# Sheet1.net
KiCad netlist of a schematic drawn in Altium Designer
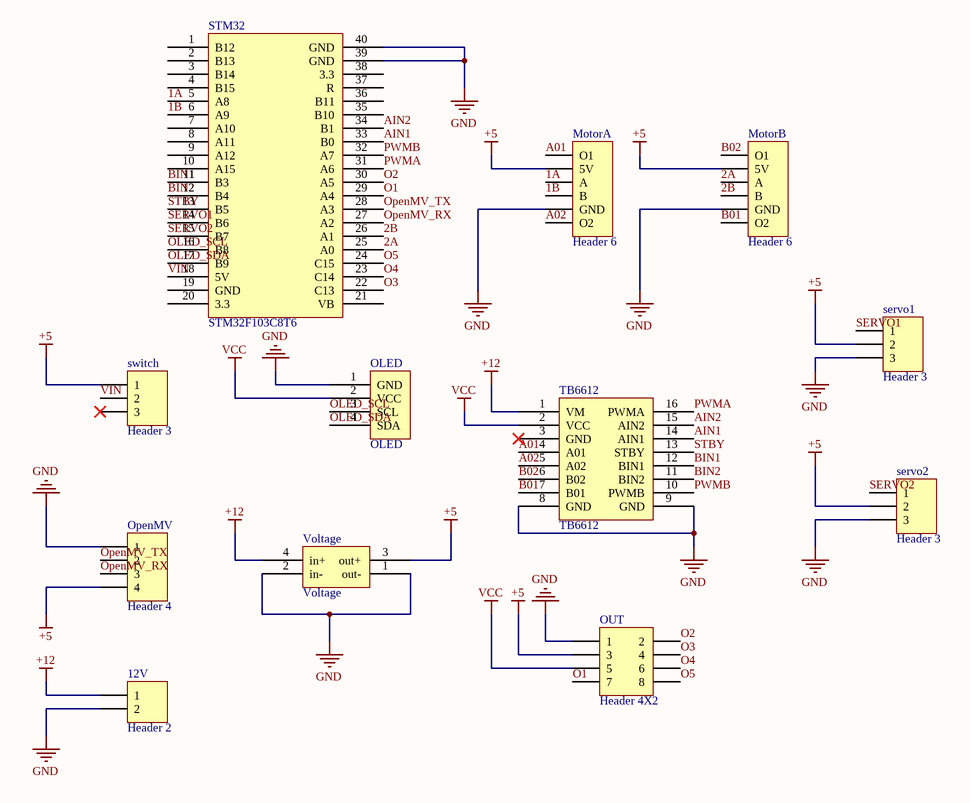
[diagram p0: Sheet1.SchDoc]

(export (version "E")
  (design (tool "Eeschema 10.0.6"))
  (components
    (comp (ref "12V")
      (value "Header 2")
      (footprint "HDR1X2")
      (description "Header, 2-Pin")
      (fields (field (name "PUBLISHER") "Altium Limited"))
      (libsource (lib "Miscellaneous Connectors") (part "Header 2"))
    )
    (comp (ref "MotorA")
      (value "Header 6")
      (footprint "HDR1X6")
      (description "Header, 6-Pin")
      (fields (field (name "PUBLISHER") "Altium Limited"))
      (libsource (lib "PCB_Project1") (part "Encoder"))
    )
    (comp (ref "MotorB")
      (value "Header 6")
      (footprint "HDR1X6")
      (description "Header, 6-Pin")
      (fields (field (name "PUBLISHER") "Altium Limited"))
      (libsource (lib "PCB_Project1") (part "Encoder"))
    )
    (comp (ref "OLED") (value "OLED") (footprint "OLED") (libsource (lib "Schlib1") (part "OLED")))
    (comp (ref "OpenMV")
      (value "Header 4")
      (footprint "HDR1X4")
      (description "Header, 4-Pin")
      (fields (field (name "PUBLISHER") "Altium Limited"))
      (libsource (lib "Miscellaneous Connectors") (part "Header 4"))
    )
    (comp (ref "OUT")
      (value "Header 4X2")
      (footprint "HDR2X4")
      (description "Header, 4-Pin, Dual row")
      (fields (field (name "PUBLISHER") "Altium Limited"))
      (libsource (lib "Miscellaneous Connectors") (part "Header 4X2"))
    )
    (comp (ref "servo1")
      (value "Header 3")
      (footprint "HDR1X3")
      (description "Header, 3-Pin")
      (fields (field (name "PUBLISHER") "Altium Limited"))
      (libsource (lib "Miscellaneous Connectors") (part "Header 3"))
    )
    (comp (ref "servo2")
      (value "Header 3")
      (footprint "HDR1X3")
      (description "Header, 3-Pin")
      (fields (field (name "PUBLISHER") "Altium Limited"))
      (libsource (lib "Miscellaneous Connectors") (part "Header 3"))
    )
    (comp (ref "STM32")
      (value "STM32F103C8T6")
      (footprint "STM32F103C8T6")
      (libsource (lib "Schlib1") (part "STM32F103C8T6"))
    )
    (comp (ref "switch")
      (value "Header 3")
      (footprint "HDR1X3")
      (description "Header, 3-Pin")
      (fields (field (name "PUBLISHER") "Altium Limited"))
      (libsource (lib "Miscellaneous Connectors") (part "Header 3"))
    )
    (comp (ref "TB6612") (value "TB6612") (footprint "TB6612") (libsource (lib "智能车主板") (part "TB6612")))
    (comp (ref "Voltage")
      (value "Voltage")
      (footprint "Voltage")
      (libsource (lib "Schlib1") (part "Voltage"))
    )
  )
  (nets
    (net (code "1") (name "+5") (class "Default")
      (node (ref "MotorA") (pin "2") (pinfunction "5V_2") (pintype "passive"))
      (node (ref "MotorB") (pin "2") (pinfunction "5V_2") (pintype "passive"))
      (node (ref "OUT") (pin "3") (pinfunction "3_3") (pintype "passive"))
      (node (ref "OpenMV") (pin "4") (pinfunction "4_4") (pintype "passive"))
      (node (ref "Voltage") (pin "3") (pinfunction "out+_3") (pintype "passive"))
      (node (ref "servo1") (pin "2") (pinfunction "2_2") (pintype "passive"))
      (node (ref "servo2") (pin "2") (pinfunction "2_2") (pintype "passive"))
      (node (ref "switch") (pin "1") (pinfunction "1_1") (pintype "passive"))
    )
    (net (code "2") (name "+12") (class "Default")
      (node (ref "12V") (pin "1") (pinfunction "1_1") (pintype "passive"))
      (node (ref "TB6612") (pin "1") (pinfunction "VM_1") (pintype "passive"))
      (node (ref "Voltage") (pin "4") (pinfunction "in+_4") (pintype "passive"))
    )
    (net (code "3") (name "/1A") (class "Default")
      (node (ref "MotorA") (pin "3") (pinfunction "A_3") (pintype "passive"))
      (node (ref "STM32") (pin "5") (pinfunction "A8_5") (pintype "passive"))
    )
    (net (code "4") (name "/1B") (class "Default")
      (node (ref "MotorA") (pin "4") (pinfunction "B_4") (pintype "passive"))
      (node (ref "STM32") (pin "6") (pinfunction "A9_6") (pintype "passive"))
    )
    (net (code "5") (name "/2A") (class "Default")
      (node (ref "MotorB") (pin "3") (pinfunction "A_3") (pintype "passive"))
      (node (ref "STM32") (pin "25") (pinfunction "A0_25") (pintype "passive"))
    )
    (net (code "6") (name "/2B") (class "Default")
      (node (ref "MotorB") (pin "4") (pinfunction "B_4") (pintype "passive"))
      (node (ref "STM32") (pin "26") (pinfunction "A1_26") (pintype "passive"))
    )
    (net (code "7") (name "/A01") (class "Default")
      (node (ref "MotorA") (pin "1") (pinfunction "O1_1") (pintype "passive"))
      (node (ref "TB6612") (pin "4") (pinfunction "A01_4") (pintype "passive"))
    )
    (net (code "8") (name "/A02") (class "Default")
      (node (ref "MotorA") (pin "6") (pinfunction "O2_6") (pintype "passive"))
      (node (ref "TB6612") (pin "5") (pinfunction "A02_5") (pintype "passive"))
    )
    (net (code "9") (name "/AIN1") (class "Default")
      (node (ref "STM32") (pin "33") (pinfunction "B0_33") (pintype "passive"))
      (node (ref "TB6612") (pin "14") (pinfunction "AIN1_14") (pintype "passive"))
    )
    (net (code "10") (name "/AIN2") (class "Default")
      (node (ref "STM32") (pin "34") (pinfunction "B1_34") (pintype "passive"))
      (node (ref "TB6612") (pin "15") (pinfunction "AIN2_15") (pintype "passive"))
    )
    (net (code "11") (name "/B01") (class "Default")
      (node (ref "MotorB") (pin "6") (pinfunction "O2_6") (pintype "passive"))
      (node (ref "TB6612") (pin "7") (pinfunction "B01_7") (pintype "passive"))
    )
    (net (code "12") (name "/B02") (class "Default")
      (node (ref "MotorB") (pin "1") (pinfunction "O1_1") (pintype "passive"))
      (node (ref "TB6612") (pin "6") (pinfunction "B02_6") (pintype "passive"))
    )
    (net (code "13") (name "/BIN1") (class "Default")
      (node (ref "STM32") (pin "11") (pinfunction "B3_11") (pintype "passive"))
      (node (ref "TB6612") (pin "12") (pinfunction "BIN1_12") (pintype "passive"))
    )
    (net (code "14") (name "/BIN2") (class "Default")
      (node (ref "STM32") (pin "12") (pinfunction "B4_12") (pintype "passive"))
      (node (ref "TB6612") (pin "11") (pinfunction "BIN2_11") (pintype "passive"))
    )
    (net (code "15") (name "/O1") (class "Default")
      (node (ref "OUT") (pin "7") (pinfunction "7_7") (pintype "passive"))
      (node (ref "STM32") (pin "29") (pinfunction "A4_29") (pintype "passive"))
    )
    (net (code "16") (name "/O2") (class "Default")
      (node (ref "OUT") (pin "2") (pinfunction "2_2") (pintype "passive"))
      (node (ref "STM32") (pin "30") (pinfunction "A5_30") (pintype "passive"))
    )
    (net (code "17") (name "/O3") (class "Default")
      (node (ref "OUT") (pin "4") (pinfunction "4_4") (pintype "passive"))
      (node (ref "STM32") (pin "22") (pinfunction "C13_22") (pintype "passive"))
    )
    (net (code "18") (name "/O4") (class "Default")
      (node (ref "OUT") (pin "6") (pinfunction "6_6") (pintype "passive"))
      (node (ref "STM32") (pin "23") (pinfunction "C14_23") (pintype "passive"))
    )
    (net (code "19") (name "/O5") (class "Default")
      (node (ref "OUT") (pin "8") (pinfunction "8_8") (pintype "passive"))
      (node (ref "STM32") (pin "24") (pinfunction "C15_24") (pintype "passive"))
    )
    (net (code "20") (name "/OLED_SCL") (class "Default")
      (node (ref "OLED") (pin "3") (pinfunction "SCL_3") (pintype "passive"))
      (node (ref "STM32") (pin "16") (pinfunction "B8_16") (pintype "passive"))
    )
    (net (code "21") (name "/OLED_SDA") (class "Default")
      (node (ref "OLED") (pin "4") (pinfunction "SDA_4") (pintype "passive"))
      (node (ref "STM32") (pin "17") (pinfunction "B9_17") (pintype "passive"))
    )
    (net (code "22") (name "/OpenMV_RX") (class "Default")
      (node (ref "OpenMV") (pin "3") (pinfunction "3_3") (pintype "passive"))
      (node (ref "STM32") (pin "27") (pinfunction "A2_27") (pintype "passive"))
    )
    (net (code "23") (name "/OpenMV_TX") (class "Default")
      (node (ref "OpenMV") (pin "2") (pinfunction "2_2") (pintype "passive"))
      (node (ref "STM32") (pin "28") (pinfunction "A3_28") (pintype "passive"))
    )
    (net (code "24") (name "/PWMA") (class "Default")
      (node (ref "STM32") (pin "31") (pinfunction "A6_31") (pintype "passive"))
      (node (ref "TB6612") (pin "16") (pinfunction "PWMA_16") (pintype "passive"))
    )
    (net (code "25") (name "/PWMB") (class "Default")
      (node (ref "STM32") (pin "32") (pinfunction "A7_32") (pintype "passive"))
      (node (ref "TB6612") (pin "10") (pinfunction "PWMB_10") (pintype "passive"))
    )
    (net (code "26") (name "/SERVO1") (class "Default")
      (node (ref "STM32") (pin "14") (pinfunction "B6_14") (pintype "passive"))
      (node (ref "servo1") (pin "1") (pinfunction "1_1") (pintype "passive"))
    )
    (net (code "27") (name "/SERVO2") (class "Default")
      (node (ref "STM32") (pin "15") (pinfunction "B7_15") (pintype "passive"))
      (node (ref "servo2") (pin "1") (pinfunction "1_1") (pintype "passive"))
    )
    (net (code "28") (name "/STBY") (class "Default")
      (node (ref "STM32") (pin "13") (pinfunction "B5_13") (pintype "passive"))
      (node (ref "TB6612") (pin "13") (pinfunction "STBY_13") (pintype "passive"))
    )
    (net (code "29") (name "/VIN") (class "Default")
      (node (ref "STM32") (pin "18") (pinfunction "5V_18") (pintype "passive"))
      (node (ref "switch") (pin "2") (pinfunction "2_2") (pintype "passive"))
    )
    (net (code "30") (name "GND") (class "Default")
      (node (ref "12V") (pin "2") (pinfunction "2_2") (pintype "passive"))
      (node (ref "MotorA") (pin "5") (pinfunction "GND_5") (pintype "passive"))
      (node (ref "MotorB") (pin "5") (pinfunction "GND_5") (pintype "passive"))
      (node (ref "OLED") (pin "1") (pinfunction "GND_1") (pintype "passive"))
      (node (ref "OUT") (pin "1") (pinfunction "1_1") (pintype "passive"))
      (node (ref "OpenMV") (pin "1") (pinfunction "1_1") (pintype "passive"))
      (node (ref "STM32") (pin "39") (pinfunction "GND_39") (pintype "passive"))
      (node (ref "STM32") (pin "40") (pinfunction "GND_40") (pintype "passive"))
      (node (ref "TB6612") (pin "8") (pinfunction "GND_8") (pintype "passive"))
      (node (ref "TB6612") (pin "9") (pinfunction "GND_9") (pintype "passive"))
      (node (ref "Voltage") (pin "1") (pinfunction "out-_1") (pintype "passive"))
      (node (ref "Voltage") (pin "2") (pinfunction "in-_2") (pintype "passive"))
      (node (ref "servo1") (pin "3") (pinfunction "3_3") (pintype "passive"))
      (node (ref "servo2") (pin "3") (pinfunction "3_3") (pintype "passive"))
    )
    (net (code "31") (name "VCC") (class "Default")
      (node (ref "OLED") (pin "2") (pinfunction "VCC_2") (pintype "passive"))
      (node (ref "OUT") (pin "5") (pinfunction "5_5") (pintype "passive"))
      (node (ref "TB6612") (pin "2") (pinfunction "VCC_2") (pintype "passive"))
    )
    (net (code "32") (name "unconnected-(STM32-3.3-Pad20)") (class "Default")
      (node (ref "STM32") (pin "20") (pinfunction "3.3_20") (pintype "passive"))
    )
    (net (code "33") (name "unconnected-(STM32-3.3-Pad38)") (class "Default")
      (node (ref "STM32") (pin "38") (pinfunction "3.3_38") (pintype "passive"))
    )
    (net (code "34") (name "unconnected-(STM32-A10-Pad7)") (class "Default")
      (node (ref "STM32") (pin "7") (pinfunction "A10_7") (pintype "passive"))
    )
    (net (code "35") (name "unconnected-(STM32-A11-Pad8)") (class "Default")
      (node (ref "STM32") (pin "8") (pinfunction "A11_8") (pintype "passive"))
    )
    (net (code "36") (name "unconnected-(STM32-A12-Pad9)") (class "Default")
      (node (ref "STM32") (pin "9") (pinfunction "A12_9") (pintype "passive"))
    )
    (net (code "37") (name "unconnected-(STM32-A15-Pad10)") (class "Default")
      (node (ref "STM32") (pin "10") (pinfunction "A15_10") (pintype "passive"))
    )
    (net (code "38") (name "unconnected-(STM32-B10-Pad35)") (class "Default")
      (node (ref "STM32") (pin "35") (pinfunction "B10_35") (pintype "passive"))
    )
    (net (code "39") (name "unconnected-(STM32-B11-Pad36)") (class "Default")
      (node (ref "STM32") (pin "36") (pinfunction "B11_36") (pintype "passive"))
    )
    (net (code "40") (name "unconnected-(STM32-B12-Pad1)") (class "Default")
      (node (ref "STM32") (pin "1") (pinfunction "B12_1") (pintype "passive"))
    )
    (net (code "41") (name "unconnected-(STM32-B13-Pad2)") (class "Default")
      (node (ref "STM32") (pin "2") (pinfunction "B13_2") (pintype "passive"))
    )
    (net (code "42") (name "unconnected-(STM32-B14-Pad3)") (class "Default")
      (node (ref "STM32") (pin "3") (pinfunction "B14_3") (pintype "passive"))
    )
    (net (code "43") (name "unconnected-(STM32-B15-Pad4)") (class "Default")
      (node (ref "STM32") (pin "4") (pinfunction "B15_4") (pintype "passive"))
    )
    (net (code "44") (name "unconnected-(STM32-GND-Pad19)") (class "Default")
      (node (ref "STM32") (pin "19") (pinfunction "GND_19") (pintype "passive"))
    )
    (net (code "45") (name "unconnected-(STM32-R-Pad37)") (class "Default")
      (node (ref "STM32") (pin "37") (pinfunction "R_37") (pintype "passive"))
    )
    (net (code "46") (name "unconnected-(STM32-VB-Pad21)") (class "Default")
      (node (ref "STM32") (pin "21") (pinfunction "VB_21") (pintype "passive"))
    )
    (net (code "47") (name "unconnected-(TB6612-GND-Pad3)") (class "Default")
      (node (ref "TB6612") (pin "3") (pinfunction "GND_3") (pintype "passive+no_connect"))
    )
    (net (code "48") (name "unconnected-(switch-Pad3)") (class "Default")
      (node (ref "switch") (pin "3") (pinfunction "3_3") (pintype "passive+no_connect"))
    )
  )
)
